# display.net
KiCad netlist of a schematic drawn in EAGLE
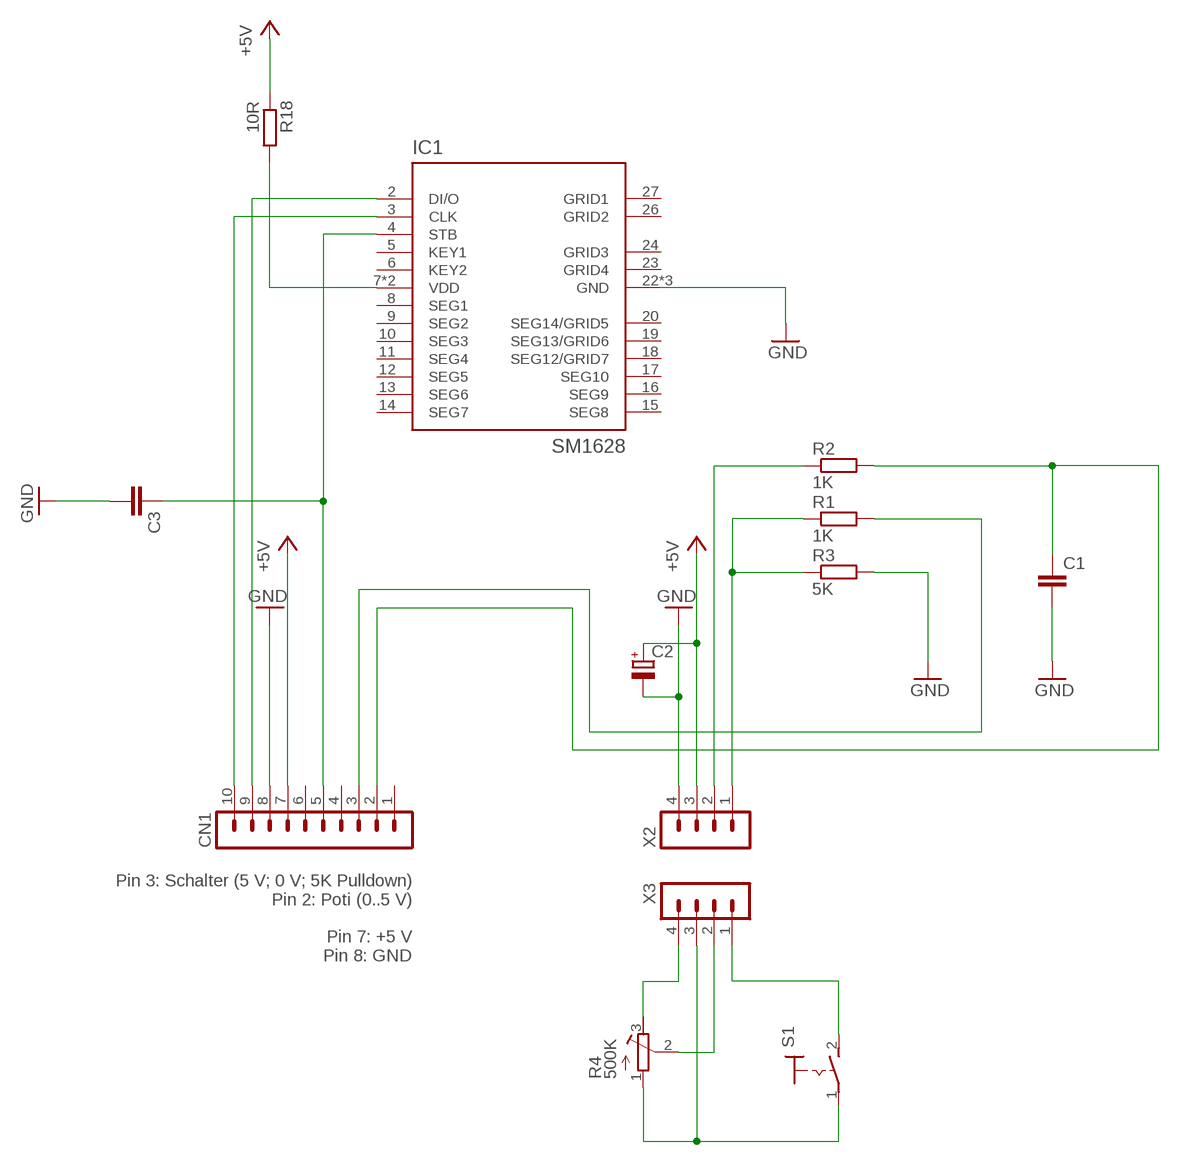
[diagram p0: schematic, sheet 1]

(export (version "E")
  (design (tool "Eeschema 10.0.6"))
  (components
    (comp (ref "C1")
      (value "C-EU050-024X044")
      (footprint "eagle-import:C050-024X044")
      (libsource (lib "eagle-import") (part "C-EU050-024X044"))
    )
    (comp (ref "C2")
      (value "CPOL-EUE2-5")
      (footprint "eagle-import:E2-5")
      (libsource (lib "eagle-import") (part "CPOL-EUE2-5"))
    )
    (comp (ref "C3")
      (value "C-EU050-024X044")
      (footprint "eagle-import:C050-024X044")
      (libsource (lib "eagle-import") (part "C-EU050-024X044"))
    )
    (comp (ref "CN1")
      (value "MA10-1")
      (footprint "eagle-import:MA10-1")
      (libsource (lib "eagle-import") (part "MA10-1"))
    )
    (comp (ref "IC1")
      (value "SM1628")
      (footprint "eagle-import:SOP28")
      (libsource (lib "eagle-import") (part "SM1628"))
    )
    (comp (ref "R1")
      (value "1K")
      (footprint "eagle-import:0207_10")
      (libsource (lib "eagle-import") (part "R-EU_0207/10"))
    )
    (comp (ref "R2")
      (value "1K")
      (footprint "eagle-import:0207_10")
      (libsource (lib "eagle-import") (part "R-EU_0207/10"))
    )
    (comp (ref "R3")
      (value "5K")
      (footprint "eagle-import:0207_10")
      (libsource (lib "eagle-import") (part "R-EU_0207/10"))
    )
    (comp (ref "R4")
      (value "500K")
      (footprint "eagle-import:RTRIM3339P")
      (libsource (lib "eagle-import") (part "R-TRIMM3339P"))
    )
    (comp (ref "R18")
      (value "10R")
      (footprint "eagle-import:0207_10")
      (libsource (lib "eagle-import") (part "R-EU_0207/10"))
    )
    (comp (ref "S1")
      (value "MS243")
      (footprint "eagle-import:MS243")
      (libsource (lib "eagle-import") (part "MS243"))
    )
    (comp (ref "X2")
      (value "MA04-1")
      (footprint "eagle-import:MA04-1")
      (libsource (lib "eagle-import") (part "MA04-1"))
    )
    (comp (ref "X3")
      (value "MA04-1")
      (footprint "eagle-import:MA04-1")
      (libsource (lib "eagle-import") (part "MA04-1"))
    )
  )
  (nets
    (net (code "1") (name "+5V") (class "Default")
      (node (ref "C2") (pin "+") (pinfunction "+_+") (pintype "passive"))
      (node (ref "CN1") (pin "7") (pinfunction "7_7") (pintype "passive"))
      (node (ref "R18") (pin "1") (pinfunction "1_1") (pintype "passive"))
      (node (ref "X2") (pin "3") (pinfunction "3_3") (pintype "passive"))
    )
    (net (code "2") (name "GND") (class "Default")
      (node (ref "C1") (pin "2") (pinfunction "2_2") (pintype "passive"))
      (node (ref "C2") (pin "-") (pinfunction "-_-") (pintype "passive"))
      (node (ref "C3") (pin "2") (pinfunction "2_2") (pintype "passive"))
      (node (ref "CN1") (pin "8") (pinfunction "8_8") (pintype "passive"))
      (node (ref "IC1") (pin "22") (pinfunction "GND_22") (pintype "bidirectional"))
      (node (ref "IC1") (pin "25") (pinfunction "GND_25") (pintype "bidirectional"))
      (node (ref "IC1") (pin "28") (pinfunction "GND_28") (pintype "bidirectional"))
      (node (ref "R3") (pin "2") (pinfunction "2_2") (pintype "passive"))
      (node (ref "X2") (pin "4") (pinfunction "4_4") (pintype "passive"))
    )
    (net (code "3") (name "Net-(C1-Pad1)") (class "Default")
      (node (ref "C1") (pin "1") (pinfunction "1_1") (pintype "passive"))
      (node (ref "CN1") (pin "2") (pinfunction "2_2") (pintype "passive"))
      (node (ref "R2") (pin "2") (pinfunction "2_2") (pintype "passive"))
    )
    (net (code "4") (name "Net-(CN1-Pad3)") (class "Default")
      (node (ref "CN1") (pin "3") (pinfunction "3_3") (pintype "passive"))
      (node (ref "R1") (pin "2") (pinfunction "2_2") (pintype "passive"))
    )
    (net (code "5") (name "Net-(IC1-CLK)") (class "Default")
      (node (ref "CN1") (pin "10") (pinfunction "10_10") (pintype "passive"))
      (node (ref "IC1") (pin "3") (pinfunction "CLK_3") (pintype "bidirectional"))
    )
    (net (code "6") (name "Net-(IC1-DI{slash}O)") (class "Default")
      (node (ref "CN1") (pin "9") (pinfunction "9_9") (pintype "passive"))
      (node (ref "IC1") (pin "2") (pinfunction "DI/O_2") (pintype "bidirectional"))
    )
    (net (code "7") (name "Net-(IC1-STB)") (class "Default")
      (node (ref "C3") (pin "1") (pinfunction "1_1") (pintype "passive"))
      (node (ref "CN1") (pin "5") (pinfunction "5_5") (pintype "passive"))
      (node (ref "IC1") (pin "4") (pinfunction "STB_4") (pintype "bidirectional"))
    )
    (net (code "8") (name "Net-(IC1-VDD-Pad21)") (class "Default")
      (node (ref "IC1") (pin "21") (pinfunction "VDD_21") (pintype "bidirectional"))
      (node (ref "IC1") (pin "7") (pinfunction "VDD_7") (pintype "bidirectional"))
      (node (ref "R18") (pin "2") (pinfunction "2_2") (pintype "passive"))
    )
    (net (code "9") (name "Net-(R1-Pad1)") (class "Default")
      (node (ref "R1") (pin "1") (pinfunction "1_1") (pintype "passive"))
      (node (ref "R3") (pin "1") (pinfunction "1_1") (pintype "passive"))
      (node (ref "X2") (pin "1") (pinfunction "1_1") (pintype "passive"))
    )
    (net (code "10") (name "Net-(R2-Pad1)") (class "Default")
      (node (ref "R2") (pin "1") (pinfunction "1_1") (pintype "passive"))
      (node (ref "X2") (pin "2") (pinfunction "2_2") (pintype "passive"))
    )
    (net (code "11") (name "Net-(R4-A)") (class "Default")
      (node (ref "R4") (pin "1") (pinfunction "A_1") (pintype "passive"))
      (node (ref "S1") (pin "1") (pinfunction "P_1") (pintype "passive"))
      (node (ref "X3") (pin "3") (pinfunction "3_3") (pintype "passive"))
    )
    (net (code "12") (name "Net-(R4-E)") (class "Default")
      (node (ref "R4") (pin "3") (pinfunction "E_3") (pintype "passive"))
      (node (ref "X3") (pin "4") (pinfunction "4_4") (pintype "passive"))
    )
    (net (code "13") (name "Net-(R4-S)") (class "Default")
      (node (ref "R4") (pin "2") (pinfunction "S_2") (pintype "passive"))
      (node (ref "X3") (pin "2") (pinfunction "2_2") (pintype "passive"))
    )
    (net (code "14") (name "Net-(S1-S)") (class "Default")
      (node (ref "S1") (pin "2") (pinfunction "S_2") (pintype "passive"))
      (node (ref "X3") (pin "1") (pinfunction "1_1") (pintype "passive"))
    )
    (net (code "15") (name "unconnected-(CN1-Pad1)") (class "Default")
      (node (ref "CN1") (pin "1") (pinfunction "1_1") (pintype "passive"))
    )
    (net (code "16") (name "unconnected-(CN1-Pad4)") (class "Default")
      (node (ref "CN1") (pin "4") (pinfunction "4_4") (pintype "passive"))
    )
    (net (code "17") (name "unconnected-(CN1-Pad6)") (class "Default")
      (node (ref "CN1") (pin "6") (pinfunction "6_6") (pintype "passive"))
    )
    (net (code "18") (name "unconnected-(IC1-GRID1-Pad27)") (class "Default")
      (node (ref "IC1") (pin "27") (pinfunction "GRID1_27") (pintype "bidirectional"))
    )
    (net (code "19") (name "unconnected-(IC1-GRID2-Pad26)") (class "Default")
      (node (ref "IC1") (pin "26") (pinfunction "GRID2_26") (pintype "bidirectional"))
    )
    (net (code "20") (name "unconnected-(IC1-GRID3-Pad24)") (class "Default")
      (node (ref "IC1") (pin "24") (pinfunction "GRID3_24") (pintype "bidirectional"))
    )
    (net (code "21") (name "unconnected-(IC1-GRID4-Pad23)") (class "Default")
      (node (ref "IC1") (pin "23") (pinfunction "GRID4_23") (pintype "bidirectional"))
    )
    (net (code "22") (name "unconnected-(IC1-KEY1-Pad5)") (class "Default")
      (node (ref "IC1") (pin "5") (pinfunction "KEY1_5") (pintype "bidirectional"))
    )
    (net (code "23") (name "unconnected-(IC1-KEY2-Pad6)") (class "Default")
      (node (ref "IC1") (pin "6") (pinfunction "KEY2_6") (pintype "bidirectional"))
    )
    (net (code "24") (name "unconnected-(IC1-SEG1-Pad8)") (class "Default")
      (node (ref "IC1") (pin "8") (pinfunction "SEG1_8") (pintype "bidirectional"))
    )
    (net (code "25") (name "unconnected-(IC1-SEG2-Pad9)") (class "Default")
      (node (ref "IC1") (pin "9") (pinfunction "SEG2_9") (pintype "bidirectional"))
    )
    (net (code "26") (name "unconnected-(IC1-SEG3-Pad10)") (class "Default")
      (node (ref "IC1") (pin "10") (pinfunction "SEG3_10") (pintype "bidirectional"))
    )
    (net (code "27") (name "unconnected-(IC1-SEG4-Pad11)") (class "Default")
      (node (ref "IC1") (pin "11") (pinfunction "SEG4_11") (pintype "bidirectional"))
    )
    (net (code "28") (name "unconnected-(IC1-SEG5-Pad12)") (class "Default")
      (node (ref "IC1") (pin "12") (pinfunction "SEG5_12") (pintype "bidirectional"))
    )
    (net (code "29") (name "unconnected-(IC1-SEG6-Pad13)") (class "Default")
      (node (ref "IC1") (pin "13") (pinfunction "SEG6_13") (pintype "bidirectional"))
    )
    (net (code "30") (name "unconnected-(IC1-SEG7-Pad14)") (class "Default")
      (node (ref "IC1") (pin "14") (pinfunction "SEG7_14") (pintype "bidirectional"))
    )
    (net (code "31") (name "unconnected-(IC1-SEG8-Pad15)") (class "Default")
      (node (ref "IC1") (pin "15") (pinfunction "SEG8_15") (pintype "bidirectional"))
    )
    (net (code "32") (name "unconnected-(IC1-SEG9-Pad16)") (class "Default")
      (node (ref "IC1") (pin "16") (pinfunction "SEG9_16") (pintype "bidirectional"))
    )
    (net (code "33") (name "unconnected-(IC1-SEG10-Pad17)") (class "Default")
      (node (ref "IC1") (pin "17") (pinfunction "SEG10_17") (pintype "bidirectional"))
    )
    (net (code "34") (name "unconnected-(IC1-SEG12{slash}GRID7-Pad18)") (class "Default")
      (node (ref "IC1") (pin "18") (pinfunction "SEG12/GRID7_18") (pintype "bidirectional"))
    )
    (net (code "35") (name "unconnected-(IC1-SEG13{slash}GRID6-Pad19)") (class "Default")
      (node (ref "IC1") (pin "19") (pinfunction "SEG13/GRID6_19") (pintype "bidirectional"))
    )
    (net (code "36") (name "unconnected-(IC1-SEG14{slash}GRID5-Pad20)") (class "Default")
      (node (ref "IC1") (pin "20") (pinfunction "SEG14/GRID5_20") (pintype "bidirectional"))
    )
  )
)
